# clk_supply.net
KiCad netlist of a schematic drawn in Altium Designer
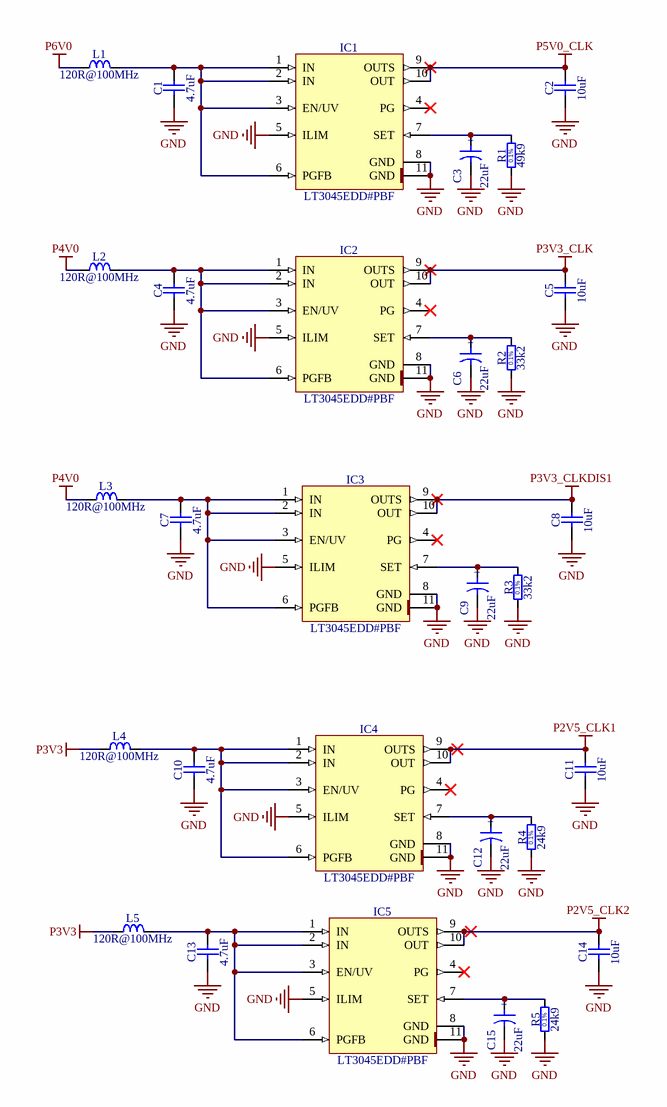
[diagram p0: clk_supply.SchDoc]

(export (version "E")
  (design (tool "Eeschema 10.0.6"))
  (components
    (comp (ref "C1")
      (value "4.7uF")
      (footprint "CAPC1608X90N")
      (description "Non-polarised capacitor")
      (fields
        (field (name "PART NUMBER") "CC0603_4.7UF_25V_10%_X5R")
        (field (name "VOLTAGE") "25V")
        (field (name "AUTHOR") "CERN DEM JLC")
      )
      (libsource (lib "Capacitors") (part "Capacitor - non polarized"))
    )
    (comp (ref "C2")
      (value "10uF")
      (footprint "CAPC1608X87N")
      (description "Non-polarised capacitor")
      (fields
        (field (name "PART NUMBER") "CC0603_10UF_6.3V_20%_X5R")
        (field (name "VOLTAGE") "6.3V")
        (field (name "AUTHOR") "CERN DEM JLC")
      )
      (libsource (lib "Capacitors") (part "Capacitor - non polarized"))
    )
    (comp (ref "C3")
      (value "22uF")
      (footprint "CAPMP3216X180N")
      (description "Polarised capacitor")
      (fields
        (field (name "PART NUMBER") "CTE3216-18_22UF_6.3V_10%_LESR0900")
        (field (name "VOLTAGE") "6.3V")
        (field (name "AUTHOR") "CERN DEM JLC")
      )
      (libsource (lib "Capacitors") (part "Capacitor - polarized"))
    )
    (comp (ref "C4")
      (value "4.7uF")
      (footprint "CAPC1608X90N")
      (description "Non-polarised capacitor")
      (fields
        (field (name "PART NUMBER") "CC0603_4.7UF_25V_10%_X5R")
        (field (name "VOLTAGE") "25V")
        (field (name "AUTHOR") "CERN DEM JLC")
      )
      (libsource (lib "Capacitors") (part "Capacitor - non polarized"))
    )
    (comp (ref "C5")
      (value "10uF")
      (footprint "CAPC1608X87N")
      (description "Non-polarised capacitor")
      (fields
        (field (name "PART NUMBER") "CC0603_10UF_6.3V_20%_X5R")
        (field (name "VOLTAGE") "6.3V")
        (field (name "AUTHOR") "CERN DEM JLC")
      )
      (libsource (lib "Capacitors") (part "Capacitor - non polarized"))
    )
    (comp (ref "C6")
      (value "22uF")
      (footprint "CAPMP3216X180N")
      (description "Polarised capacitor")
      (fields
        (field (name "PART NUMBER") "CTE3216-18_22UF_6.3V_10%_LESR0900")
        (field (name "VOLTAGE") "6.3V")
        (field (name "AUTHOR") "CERN DEM JLC")
      )
      (libsource (lib "Capacitors") (part "Capacitor - polarized"))
    )
    (comp (ref "C7")
      (value "4.7uF")
      (footprint "CAPC1608X90N")
      (description "Non-polarised capacitor")
      (fields
        (field (name "PART NUMBER") "CC0603_4.7UF_25V_10%_X5R")
        (field (name "VOLTAGE") "25V")
        (field (name "AUTHOR") "CERN DEM JLC")
      )
      (libsource (lib "Capacitors") (part "Capacitor - non polarized"))
    )
    (comp (ref "C8")
      (value "10uF")
      (footprint "CAPC1608X87N")
      (description "Non-polarised capacitor")
      (fields
        (field (name "PART NUMBER") "CC0603_10UF_6.3V_20%_X5R")
        (field (name "VOLTAGE") "6.3V")
        (field (name "AUTHOR") "CERN DEM JLC")
      )
      (libsource (lib "Capacitors") (part "Capacitor - non polarized"))
    )
    (comp (ref "C9")
      (value "22uF")
      (footprint "CAPMP3216X180N")
      (description "Polarised capacitor")
      (fields
        (field (name "PART NUMBER") "CTE3216-18_22UF_6.3V_10%_LESR0900")
        (field (name "VOLTAGE") "6.3V")
        (field (name "AUTHOR") "CERN DEM JLC")
      )
      (libsource (lib "Capacitors") (part "Capacitor - polarized"))
    )
    (comp (ref "C10")
      (value "4.7uF")
      (footprint "CAPC1608X90N")
      (description "Non-polarised capacitor")
      (fields
        (field (name "PART NUMBER") "CC0603_4.7UF_25V_10%_X5R")
        (field (name "VOLTAGE") "25V")
        (field (name "AUTHOR") "CERN DEM JLC")
      )
      (libsource (lib "Capacitors") (part "Capacitor - non polarized"))
    )
    (comp (ref "C11")
      (value "10uF")
      (footprint "CAPC1608X87N")
      (description "Non-polarised capacitor")
      (fields
        (field (name "PART NUMBER") "CC0603_10UF_6.3V_20%_X5R")
        (field (name "VOLTAGE") "6.3V")
        (field (name "AUTHOR") "CERN DEM JLC")
      )
      (libsource (lib "Capacitors") (part "Capacitor - non polarized"))
    )
    (comp (ref "C12")
      (value "22uF")
      (footprint "CAPMP3216X180N")
      (description "Polarised capacitor")
      (fields
        (field (name "PART NUMBER") "CTE3216-18_22UF_6.3V_10%_LESR0900")
        (field (name "VOLTAGE") "6.3V")
        (field (name "AUTHOR") "CERN DEM JLC")
      )
      (libsource (lib "Capacitors") (part "Capacitor - polarized"))
    )
    (comp (ref "C13")
      (value "4.7uF")
      (footprint "CAPC1608X90N")
      (description "Non-polarised capacitor")
      (fields
        (field (name "PART NUMBER") "CC0603_4.7UF_25V_10%_X5R")
        (field (name "VOLTAGE") "25V")
        (field (name "AUTHOR") "CERN DEM JLC")
      )
      (libsource (lib "Capacitors") (part "Capacitor - non polarized"))
    )
    (comp (ref "C14")
      (value "10uF")
      (footprint "CAPC1608X87N")
      (description "Non-polarised capacitor")
      (fields
        (field (name "PART NUMBER") "CC0603_10UF_6.3V_20%_X5R")
        (field (name "VOLTAGE") "6.3V")
        (field (name "AUTHOR") "CERN DEM JLC")
      )
      (libsource (lib "Capacitors") (part "Capacitor - non polarized"))
    )
    (comp (ref "C15")
      (value "22uF")
      (footprint "CAPMP3216X180N")
      (description "Polarised capacitor")
      (fields
        (field (name "PART NUMBER") "CTE3216-18_22UF_6.3V_10%_LESR0900")
        (field (name "VOLTAGE") "6.3V")
        (field (name "AUTHOR") "CERN DEM JLC")
      )
      (libsource (lib "Capacitors") (part "Capacitor - polarized"))
    )
    (comp (ref "IC1")
      (value "LT3045EDD#PBF")
      (footprint "SON50P300X300X80-11N-R175X248")
      (description "20V, 500mA, Ultralow Noise, Ultrahigh PSRR Linear Regulator")
      (fields (field (name "MANUFACTURER") "LINEAR TECHNOLOGY") (field (name "AUTHOR") "CERN DEM JLC"))
      (libsource (lib "ICs And Semiconductors") (part "LT3045EDD"))
    )
    (comp (ref "IC2")
      (value "LT3045EDD#PBF")
      (footprint "SON50P300X300X80-11N-R175X248")
      (description "20V, 500mA, Ultralow Noise, Ultrahigh PSRR Linear Regulator")
      (fields (field (name "MANUFACTURER") "LINEAR TECHNOLOGY") (field (name "AUTHOR") "CERN DEM JLC"))
      (libsource (lib "ICs And Semiconductors") (part "LT3045EDD"))
    )
    (comp (ref "IC3")
      (value "LT3045EDD#PBF")
      (footprint "SON50P300X300X80-11N-R175X248")
      (description "20V, 500mA, Ultralow Noise, Ultrahigh PSRR Linear Regulator")
      (fields (field (name "MANUFACTURER") "LINEAR TECHNOLOGY") (field (name "AUTHOR") "CERN DEM JLC"))
      (libsource (lib "ICs And Semiconductors") (part "LT3045EDD"))
    )
    (comp (ref "IC4")
      (value "LT3045EDD#PBF")
      (footprint "SON50P300X300X80-11N-R175X248")
      (description "20V, 500mA, Ultralow Noise, Ultrahigh PSRR Linear Regulator")
      (fields (field (name "MANUFACTURER") "LINEAR TECHNOLOGY") (field (name "AUTHOR") "CERN DEM JLC"))
      (libsource (lib "ICs And Semiconductors") (part "LT3045EDD"))
    )
    (comp (ref "IC5")
      (value "LT3045EDD#PBF")
      (footprint "SON50P300X300X80-11N-R175X248")
      (description "20V, 500mA, Ultralow Noise, Ultrahigh PSRR Linear Regulator")
      (fields (field (name "MANUFACTURER") "LINEAR TECHNOLOGY") (field (name "AUTHOR") "CERN DEM JLC"))
      (libsource (lib "ICs And Semiconductors") (part "LT3045EDD"))
    )
    (comp (ref "L1")
      (value "120R@100MHz")
      (footprint "INDC1608X95N")
      (description "Inductor")
      (fields
        (field (name "PART NUMBER") "IND0603_MURATA_BLM18PG121SN1D")
        (field (name "POWER") "2A")
        (field (name "AUTHOR") "CERN DEM BC")
      )
      (libsource (lib "Inductors & Transformers") (part "Inductor"))
    )
    (comp (ref "L2")
      (value "120R@100MHz")
      (footprint "INDC1608X95N")
      (description "Inductor")
      (fields
        (field (name "PART NUMBER") "IND0603_MURATA_BLM18PG121SN1D")
        (field (name "POWER") "2A")
        (field (name "AUTHOR") "CERN DEM BC")
      )
      (libsource (lib "Inductors & Transformers") (part "Inductor"))
    )
    (comp (ref "L3")
      (value "120R@100MHz")
      (footprint "INDC1608X95N")
      (description "Inductor")
      (fields
        (field (name "PART NUMBER") "IND0603_MURATA_BLM18PG121SN1D")
        (field (name "POWER") "2A")
        (field (name "AUTHOR") "CERN DEM BC")
      )
      (libsource (lib "Inductors & Transformers") (part "Inductor"))
    )
    (comp (ref "L4")
      (value "120R@100MHz")
      (footprint "INDC1608X95N")
      (description "Inductor")
      (fields
        (field (name "PART NUMBER") "IND0603_MURATA_BLM18PG121SN1D")
        (field (name "POWER") "2A")
        (field (name "AUTHOR") "CERN DEM BC")
      )
      (libsource (lib "Inductors & Transformers") (part "Inductor"))
    )
    (comp (ref "L5")
      (value "120R@100MHz")
      (footprint "INDC1608X95N")
      (description "Inductor")
      (fields
        (field (name "PART NUMBER") "IND0603_MURATA_BLM18PG121SN1D")
        (field (name "POWER") "2A")
        (field (name "AUTHOR") "CERN DEM BC")
      )
      (libsource (lib "Inductors & Transformers") (part "Inductor"))
    )
    (comp (ref "R1")
      (value "49k9")
      (footprint "RESC1608X55N")
      (description "Resistor - 0.1%")
      (fields
        (field (name "PART NUMBER") "R0603_49K9_0.1%_0.063W_10PPM")
        (field (name "POWER") "0.063W")
        (field (name "AUTHOR") "CERN DEM JLC")
      )
      (libsource (lib "Resistors") (part "Resistor - 0.1%"))
    )
    (comp (ref "R2")
      (value "33k2")
      (footprint "RESC1608X55N")
      (description "Resistor - 0.1%")
      (fields
        (field (name "PART NUMBER") "R0603_33K2_0.1%_0.063W_10PPM")
        (field (name "POWER") "0.063W")
        (field (name "AUTHOR") "CERN DEM JLC")
      )
      (libsource (lib "Resistors") (part "Resistor - 0.1%"))
    )
    (comp (ref "R3")
      (value "33k2")
      (footprint "RESC1608X55N")
      (description "Resistor - 0.1%")
      (fields
        (field (name "PART NUMBER") "R0603_33K2_0.1%_0.063W_10PPM")
        (field (name "POWER") "0.063W")
        (field (name "AUTHOR") "CERN DEM JLC")
      )
      (libsource (lib "Resistors") (part "Resistor - 0.1%"))
    )
    (comp (ref "R4")
      (value "24k9")
      (footprint "RESC1608X55N")
      (description "Resistor - 0.1%")
      (fields
        (field (name "PART NUMBER") "R0603_24K9_0.1%_0.063W_10PPM")
        (field (name "POWER") "0.063W")
        (field (name "AUTHOR") "CERN DEM JLC")
      )
      (libsource (lib "Resistors") (part "Resistor - 0.1%"))
    )
    (comp (ref "R5")
      (value "24k9")
      (footprint "RESC1608X55N")
      (description "Resistor - 0.1%")
      (fields
        (field (name "PART NUMBER") "R0603_24K9_0.1%_0.063W_10PPM")
        (field (name "POWER") "0.063W")
        (field (name "AUTHOR") "CERN DEM JLC")
      )
      (libsource (lib "Resistors") (part "Resistor - 0.1%"))
    )
  )
  (nets
    (net (code "1") (name "GND") (class "Default")
      (node (ref "C1") (pin "1") (pinfunction "1_1") (pintype "passive"))
      (node (ref "C10") (pin "1") (pinfunction "1_1") (pintype "passive"))
      (node (ref "C11") (pin "1") (pinfunction "1_1") (pintype "passive"))
      (node (ref "C12") (pin "2") (pinfunction "2_2") (pintype "passive"))
      (node (ref "C13") (pin "1") (pinfunction "1_1") (pintype "passive"))
      (node (ref "C14") (pin "1") (pinfunction "1_1") (pintype "passive"))
      (node (ref "C15") (pin "2") (pinfunction "2_2") (pintype "passive"))
      (node (ref "C2") (pin "1") (pinfunction "1_1") (pintype "passive"))
      (node (ref "C3") (pin "2") (pinfunction "2_2") (pintype "passive"))
      (node (ref "C4") (pin "1") (pinfunction "1_1") (pintype "passive"))
      (node (ref "C5") (pin "1") (pinfunction "1_1") (pintype "passive"))
      (node (ref "C6") (pin "2") (pinfunction "2_2") (pintype "passive"))
      (node (ref "C7") (pin "1") (pinfunction "1_1") (pintype "passive"))
      (node (ref "C8") (pin "1") (pinfunction "1_1") (pintype "passive"))
      (node (ref "C9") (pin "2") (pinfunction "2_2") (pintype "passive"))
      (node (ref "IC1") (pin "11") (pinfunction "GND_11") (pintype "power_in"))
      (node (ref "IC1") (pin "5") (pinfunction "ILIM_5") (pintype "input"))
      (node (ref "IC1") (pin "8") (pinfunction "GND_8") (pintype "power_in"))
      (node (ref "IC2") (pin "11") (pinfunction "GND_11") (pintype "power_in"))
      (node (ref "IC2") (pin "5") (pinfunction "ILIM_5") (pintype "input"))
      (node (ref "IC2") (pin "8") (pinfunction "GND_8") (pintype "power_in"))
      (node (ref "IC3") (pin "11") (pinfunction "GND_11") (pintype "power_in"))
      (node (ref "IC3") (pin "5") (pinfunction "ILIM_5") (pintype "input"))
      (node (ref "IC3") (pin "8") (pinfunction "GND_8") (pintype "power_in"))
      (node (ref "IC4") (pin "11") (pinfunction "GND_11") (pintype "power_in"))
      (node (ref "IC4") (pin "5") (pinfunction "ILIM_5") (pintype "input"))
      (node (ref "IC4") (pin "8") (pinfunction "GND_8") (pintype "power_in"))
      (node (ref "IC5") (pin "11") (pinfunction "GND_11") (pintype "power_in"))
      (node (ref "IC5") (pin "5") (pinfunction "ILIM_5") (pintype "input"))
      (node (ref "IC5") (pin "8") (pinfunction "GND_8") (pintype "power_in"))
      (node (ref "R1") (pin "1") (pinfunction "1_1") (pintype "passive"))
      (node (ref "R2") (pin "1") (pinfunction "1_1") (pintype "passive"))
      (node (ref "R3") (pin "1") (pinfunction "1_1") (pintype "passive"))
      (node (ref "R4") (pin "1") (pinfunction "1_1") (pintype "passive"))
      (node (ref "R5") (pin "1") (pinfunction "1_1") (pintype "passive"))
    )
    (net (code "2") (name "Net-(IC1-EN{slash}UV)") (class "Default")
      (node (ref "C1") (pin "2") (pinfunction "2_2") (pintype "passive"))
      (node (ref "IC1") (pin "1") (pinfunction "IN_1") (pintype "input"))
      (node (ref "IC1") (pin "2") (pinfunction "IN_2") (pintype "input"))
      (node (ref "IC1") (pin "3") (pinfunction "EN/UV_3") (pintype "input"))
      (node (ref "IC1") (pin "6") (pinfunction "PGFB_6") (pintype "input"))
      (node (ref "L1") (pin "2") (pinfunction "2_2") (pintype "passive"))
    )
    (net (code "3") (name "Net-(IC1-SET)") (class "Default")
      (node (ref "C3") (pin "1") (pinfunction "1_1") (pintype "passive"))
      (node (ref "IC1") (pin "7") (pinfunction "SET_7") (pintype "input"))
      (node (ref "R1") (pin "2") (pinfunction "2_2") (pintype "passive"))
    )
    (net (code "4") (name "Net-(IC2-EN{slash}UV)") (class "Default")
      (node (ref "C4") (pin "2") (pinfunction "2_2") (pintype "passive"))
      (node (ref "IC2") (pin "1") (pinfunction "IN_1") (pintype "input"))
      (node (ref "IC2") (pin "2") (pinfunction "IN_2") (pintype "input"))
      (node (ref "IC2") (pin "3") (pinfunction "EN/UV_3") (pintype "input"))
      (node (ref "IC2") (pin "6") (pinfunction "PGFB_6") (pintype "input"))
      (node (ref "L2") (pin "2") (pinfunction "2_2") (pintype "passive"))
    )
    (net (code "5") (name "Net-(IC2-SET)") (class "Default")
      (node (ref "C6") (pin "1") (pinfunction "1_1") (pintype "passive"))
      (node (ref "IC2") (pin "7") (pinfunction "SET_7") (pintype "input"))
      (node (ref "R2") (pin "2") (pinfunction "2_2") (pintype "passive"))
    )
    (net (code "6") (name "Net-(IC3-EN{slash}UV)") (class "Default")
      (node (ref "C7") (pin "2") (pinfunction "2_2") (pintype "passive"))
      (node (ref "IC3") (pin "1") (pinfunction "IN_1") (pintype "input"))
      (node (ref "IC3") (pin "2") (pinfunction "IN_2") (pintype "input"))
      (node (ref "IC3") (pin "3") (pinfunction "EN/UV_3") (pintype "input"))
      (node (ref "IC3") (pin "6") (pinfunction "PGFB_6") (pintype "input"))
      (node (ref "L3") (pin "2") (pinfunction "2_2") (pintype "passive"))
    )
    (net (code "7") (name "Net-(IC3-SET)") (class "Default")
      (node (ref "C9") (pin "1") (pinfunction "1_1") (pintype "passive"))
      (node (ref "IC3") (pin "7") (pinfunction "SET_7") (pintype "input"))
      (node (ref "R3") (pin "2") (pinfunction "2_2") (pintype "passive"))
    )
    (net (code "8") (name "Net-(IC4-EN{slash}UV)") (class "Default")
      (node (ref "C10") (pin "2") (pinfunction "2_2") (pintype "passive"))
      (node (ref "IC4") (pin "1") (pinfunction "IN_1") (pintype "input"))
      (node (ref "IC4") (pin "2") (pinfunction "IN_2") (pintype "input"))
      (node (ref "IC4") (pin "3") (pinfunction "EN/UV_3") (pintype "input"))
      (node (ref "IC4") (pin "6") (pinfunction "PGFB_6") (pintype "input"))
      (node (ref "L4") (pin "2") (pinfunction "2_2") (pintype "passive"))
    )
    (net (code "9") (name "Net-(IC4-SET)") (class "Default")
      (node (ref "C12") (pin "1") (pinfunction "1_1") (pintype "passive"))
      (node (ref "IC4") (pin "7") (pinfunction "SET_7") (pintype "input"))
      (node (ref "R4") (pin "2") (pinfunction "2_2") (pintype "passive"))
    )
    (net (code "10") (name "Net-(IC5-EN{slash}UV)") (class "Default")
      (node (ref "C13") (pin "2") (pinfunction "2_2") (pintype "passive"))
      (node (ref "IC5") (pin "1") (pinfunction "IN_1") (pintype "input"))
      (node (ref "IC5") (pin "2") (pinfunction "IN_2") (pintype "input"))
      (node (ref "IC5") (pin "3") (pinfunction "EN/UV_3") (pintype "input"))
      (node (ref "IC5") (pin "6") (pinfunction "PGFB_6") (pintype "input"))
      (node (ref "L5") (pin "2") (pinfunction "2_2") (pintype "passive"))
    )
    (net (code "11") (name "Net-(IC5-SET)") (class "Default")
      (node (ref "C15") (pin "1") (pinfunction "1_1") (pintype "passive"))
      (node (ref "IC5") (pin "7") (pinfunction "SET_7") (pintype "input"))
      (node (ref "R5") (pin "2") (pinfunction "2_2") (pintype "passive"))
    )
    (net (code "12") (name "P2V5_CLK1") (class "Default")
      (node (ref "C11") (pin "2") (pinfunction "2_2") (pintype "passive"))
      (node (ref "IC4") (pin "10") (pinfunction "OUT_10") (pintype "output"))
      (node (ref "IC4") (pin "9") (pinfunction "OUTS_9") (pintype "output"))
    )
    (net (code "13") (name "P2V5_CLK2") (class "Default")
      (node (ref "C14") (pin "2") (pinfunction "2_2") (pintype "passive"))
      (node (ref "IC5") (pin "10") (pinfunction "OUT_10") (pintype "output"))
      (node (ref "IC5") (pin "9") (pinfunction "OUTS_9") (pintype "output"))
    )
    (net (code "14") (name "P3V3") (class "Default")
      (node (ref "L4") (pin "1") (pinfunction "1_1") (pintype "passive"))
      (node (ref "L5") (pin "1") (pinfunction "1_1") (pintype "passive"))
    )
    (net (code "15") (name "P3V3_CLK") (class "Default")
      (node (ref "C5") (pin "2") (pinfunction "2_2") (pintype "passive"))
      (node (ref "IC2") (pin "10") (pinfunction "OUT_10") (pintype "output"))
      (node (ref "IC2") (pin "9") (pinfunction "OUTS_9") (pintype "output"))
    )
    (net (code "16") (name "P3V3_CLKDIS1") (class "Default")
      (node (ref "C8") (pin "2") (pinfunction "2_2") (pintype "passive"))
      (node (ref "IC3") (pin "10") (pinfunction "OUT_10") (pintype "output"))
      (node (ref "IC3") (pin "9") (pinfunction "OUTS_9") (pintype "output"))
    )
    (net (code "17") (name "P4V0") (class "Default")
      (node (ref "L2") (pin "1") (pinfunction "1_1") (pintype "passive"))
      (node (ref "L3") (pin "1") (pinfunction "1_1") (pintype "passive"))
    )
    (net (code "18") (name "P5V0_CLK") (class "Default")
      (node (ref "C2") (pin "2") (pinfunction "2_2") (pintype "passive"))
      (node (ref "IC1") (pin "10") (pinfunction "OUT_10") (pintype "output"))
      (node (ref "IC1") (pin "9") (pinfunction "OUTS_9") (pintype "output"))
    )
    (net (code "19") (name "P6V0") (class "Default")
      (node (ref "L1") (pin "1") (pinfunction "1_1") (pintype "passive"))
    )
    (net (code "20") (name "unconnected-(IC1-PG-Pad4)") (class "Default")
      (node (ref "IC1") (pin "4") (pinfunction "PG_4") (pintype "output+no_connect"))
    )
    (net (code "21") (name "unconnected-(IC2-PG-Pad4)") (class "Default")
      (node (ref "IC2") (pin "4") (pinfunction "PG_4") (pintype "output+no_connect"))
    )
    (net (code "22") (name "unconnected-(IC3-PG-Pad4)") (class "Default")
      (node (ref "IC3") (pin "4") (pinfunction "PG_4") (pintype "output+no_connect"))
    )
    (net (code "23") (name "unconnected-(IC4-PG-Pad4)") (class "Default")
      (node (ref "IC4") (pin "4") (pinfunction "PG_4") (pintype "output+no_connect"))
    )
    (net (code "24") (name "unconnected-(IC5-PG-Pad4)") (class "Default")
      (node (ref "IC5") (pin "4") (pinfunction "PG_4") (pintype "output+no_connect"))
    )
  )
)
